# expansion.net
KiCad netlist of a schematic drawn in Altium Designer
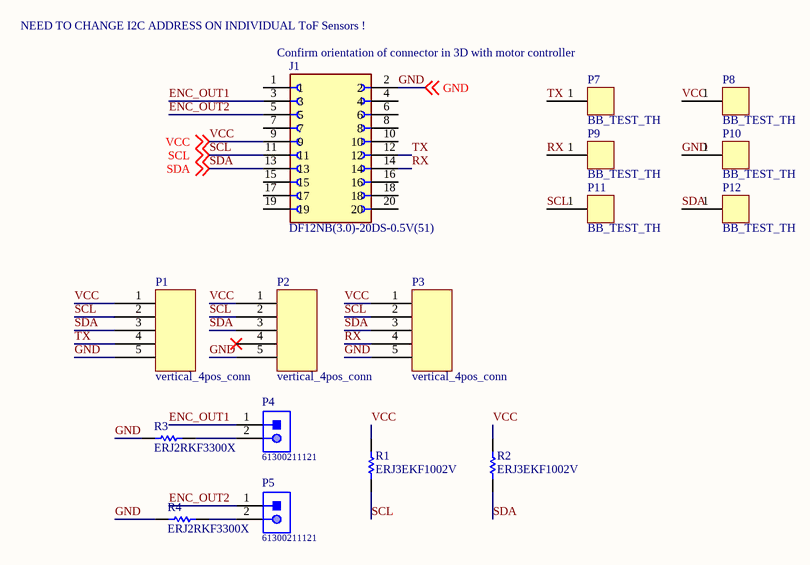
[diagram p0: expansion.SchDoc]

(export (version "E")
  (design (tool "Eeschema 10.0.6"))
  (components
    (comp (ref "J1")
      (value "DF12NB(3.0)-20DS-0.5V(51)")
      (footprint "HRS_DF12NB(3.0)-20DS-0.5V(51)")
      (libsource (lib "expansion_library") (part "DF12NB(3.0)-20DS-0.5V(51)"))
    )
    (comp (ref "P1")
      (value "vertical_4pos_conn")
      (footprint "vertical_4pos_conn _s_square")
      (libsource (lib "expansion_library") (part "vertical_4pos_conn"))
    )
    (comp (ref "P2")
      (value "vertical_4pos_conn")
      (footprint "vertical_4pos_conn _s_square")
      (libsource (lib "expansion_library") (part "vertical_4pos_conn"))
    )
    (comp (ref "P3")
      (value "vertical_4pos_conn")
      (footprint "vertical_4pos_conn _s_square")
      (libsource (lib "expansion_library") (part "vertical_4pos_conn"))
    )
    (comp (ref "P4")
      (value "61300211121")
      (footprint "61300211121")
      (description "THT Vertical Pin Header WR-PHD, Pitch 2.54 mm, Single Row, 2 pins")
      (fields (field (name "MANUFACTURER") "Wurth Elektronik") (field (name "PUBLISHER") "WurthElektronik"))
      (libsource (lib "Altium Content Vault") (part "WE-CN-1P-M-R2"))
    )
    (comp (ref "P5")
      (value "61300211121")
      (footprint "61300211121")
      (description "THT Vertical Pin Header WR-PHD, Pitch 2.54 mm, Single Row, 2 pins")
      (fields (field (name "MANUFACTURER") "Wurth Elektronik") (field (name "PUBLISHER") "WurthElektronik"))
      (libsource (lib "Altium Content Vault") (part "WE-CN-1P-M-R2"))
    )
    (comp (ref "P7")
      (value "BB_TEST_TH")
      (footprint "BB_WIRE_TEST_TH")
      (libsource (lib "expansion_library") (part "BB_TEST_TH"))
    )
    (comp (ref "P8")
      (value "BB_TEST_TH")
      (footprint "BB_WIRE_TEST_TH")
      (libsource (lib "expansion_library") (part "BB_TEST_TH"))
    )
    (comp (ref "P9")
      (value "BB_TEST_TH")
      (footprint "BB_WIRE_TEST_TH")
      (libsource (lib "expansion_library") (part "BB_TEST_TH"))
    )
    (comp (ref "P10")
      (value "BB_TEST_TH")
      (footprint "BB_WIRE_TEST_TH")
      (libsource (lib "expansion_library") (part "BB_TEST_TH"))
    )
    (comp (ref "P11")
      (value "BB_TEST_TH")
      (footprint "BB_WIRE_TEST_TH")
      (libsource (lib "expansion_library") (part "BB_TEST_TH"))
    )
    (comp (ref "P12")
      (value "BB_TEST_TH")
      (footprint "BB_WIRE_TEST_TH")
      (libsource (lib "expansion_library") (part "BB_TEST_TH"))
    )
    (comp (ref "R1")
      (value "ERJ3EKF1002V")
      (footprint "RESC1609X55X30LL15T15")
      (description "Chip Resistor, 10 KOhm, +/- 1%, 0.1 W, -55 to 155 degC, 0603 (1608 Metric), RoHS, Tape and Reel")
      (fields (field (name "TOLERANCE") "1%") (field (name "MANUFACTURER") "Panasonic"))
      (libsource (lib "Altium Content Vault") (part "RES-2"))
    )
    (comp (ref "R2")
      (value "ERJ3EKF1002V")
      (footprint "RESC1609X55X30LL15T15")
      (description "Chip Resistor, 10 KOhm, +/- 1%, 0.1 W, -55 to 155 degC, 0603 (1608 Metric), RoHS, Tape and Reel")
      (fields (field (name "TOLERANCE") "1%") (field (name "MANUFACTURER") "Panasonic"))
      (libsource (lib "Altium Content Vault") (part "RES-2"))
    )
    (comp (ref "R3")
      (value "ERJ2RKF3300X")
      (footprint "RESC1005X40X25ML05T05")
      (fields (field (name "MANUFACTURER") "Panasonic"))
      (libsource (lib "Altium Content Vault") (part "RES"))
    )
    (comp (ref "R4")
      (value "ERJ2RKF3300X")
      (footprint "RESC1005X40X25ML05T05")
      (fields (field (name "MANUFACTURER") "Panasonic"))
      (libsource (lib "Altium Content Vault") (part "RES"))
    )
  )
  (nets
    (net (code "1") (name "/ENC_OUT1") (class "Default")
      (node (ref "J1") (pin "3") (pinfunction "3_3") (pintype "passive"))
      (node (ref "P4") (pin "1") (pinfunction "1_1") (pintype "passive"))
    )
    (net (code "2") (name "/ENC_OUT2") (class "Default")
      (node (ref "J1") (pin "5") (pinfunction "5_5") (pintype "passive"))
      (node (ref "P5") (pin "1") (pinfunction "1_1") (pintype "passive"))
    )
    (net (code "3") (name "/RX") (class "Default")
      (node (ref "J1") (pin "14") (pinfunction "14_14") (pintype "passive"))
      (node (ref "P3") (pin "4") (pinfunction "4_4") (pintype "passive"))
      (node (ref "P9") (pin "1") (pinfunction "1_1") (pintype "passive"))
    )
    (net (code "4") (name "/TX") (class "Default")
      (node (ref "J1") (pin "12") (pinfunction "12_12") (pintype "passive"))
      (node (ref "P1") (pin "4") (pinfunction "4_4") (pintype "passive"))
      (node (ref "P7") (pin "1") (pinfunction "1_1") (pintype "passive"))
    )
    (net (code "5") (name "GND") (class "Default")
      (node (ref "J1") (pin "2") (pinfunction "2_2") (pintype "passive"))
      (node (ref "P1") (pin "5") (pinfunction "5_5") (pintype "passive"))
      (node (ref "P10") (pin "1") (pinfunction "1_1") (pintype "passive"))
      (node (ref "P2") (pin "5") (pinfunction "5_5") (pintype "passive"))
      (node (ref "P3") (pin "5") (pinfunction "5_5") (pintype "passive"))
      (node (ref "R3") (pin "1") (pinfunction "1_1") (pintype "passive"))
      (node (ref "R4") (pin "1") (pinfunction "1_1") (pintype "passive"))
    )
    (net (code "6") (name "Net-(P4-Pad2)") (class "Default")
      (node (ref "P4") (pin "2") (pinfunction "2_2") (pintype "passive"))
      (node (ref "R3") (pin "2") (pinfunction "2_2") (pintype "passive"))
    )
    (net (code "7") (name "Net-(P5-Pad2)") (class "Default")
      (node (ref "P5") (pin "2") (pinfunction "2_2") (pintype "passive"))
      (node (ref "R4") (pin "2") (pinfunction "2_2") (pintype "passive"))
    )
    (net (code "8") (name "SCL") (class "Default")
      (node (ref "J1") (pin "11") (pinfunction "11_11") (pintype "passive"))
      (node (ref "P1") (pin "2") (pinfunction "2_2") (pintype "passive"))
      (node (ref "P11") (pin "1") (pinfunction "1_1") (pintype "passive"))
      (node (ref "P2") (pin "2") (pinfunction "2_2") (pintype "passive"))
      (node (ref "P3") (pin "2") (pinfunction "2_2") (pintype "passive"))
      (node (ref "R1") (pin "1") (pinfunction "1_1") (pintype "passive"))
    )
    (net (code "9") (name "SDA") (class "Default")
      (node (ref "J1") (pin "13") (pinfunction "13_13") (pintype "passive"))
      (node (ref "P1") (pin "3") (pinfunction "3_3") (pintype "passive"))
      (node (ref "P12") (pin "1") (pinfunction "1_1") (pintype "passive"))
      (node (ref "P2") (pin "3") (pinfunction "3_3") (pintype "passive"))
      (node (ref "P3") (pin "3") (pinfunction "3_3") (pintype "passive"))
      (node (ref "R2") (pin "1") (pinfunction "1_1") (pintype "passive"))
    )
    (net (code "10") (name "VCC") (class "Default")
      (node (ref "J1") (pin "9") (pinfunction "9_9") (pintype "passive"))
      (node (ref "P1") (pin "1") (pinfunction "1_1") (pintype "passive"))
      (node (ref "P2") (pin "1") (pinfunction "1_1") (pintype "passive"))
      (node (ref "P3") (pin "1") (pinfunction "1_1") (pintype "passive"))
      (node (ref "P8") (pin "1") (pinfunction "1_1") (pintype "passive"))
      (node (ref "R1") (pin "2") (pinfunction "2_2") (pintype "passive"))
      (node (ref "R2") (pin "2") (pinfunction "2_2") (pintype "passive"))
    )
    (net (code "11") (name "unconnected-(J1-Pad1)") (class "Default")
      (node (ref "J1") (pin "1") (pinfunction "1_1") (pintype "passive"))
    )
    (net (code "12") (name "unconnected-(J1-Pad4)") (class "Default")
      (node (ref "J1") (pin "4") (pinfunction "4_4") (pintype "passive"))
    )
    (net (code "13") (name "unconnected-(J1-Pad6)") (class "Default")
      (node (ref "J1") (pin "6") (pinfunction "6_6") (pintype "passive"))
    )
    (net (code "14") (name "unconnected-(J1-Pad7)") (class "Default")
      (node (ref "J1") (pin "7") (pinfunction "7_7") (pintype "passive"))
    )
    (net (code "15") (name "unconnected-(J1-Pad8)") (class "Default")
      (node (ref "J1") (pin "8") (pinfunction "8_8") (pintype "passive"))
    )
    (net (code "16") (name "unconnected-(J1-Pad10)") (class "Default")
      (node (ref "J1") (pin "10") (pinfunction "10_10") (pintype "passive"))
    )
    (net (code "17") (name "unconnected-(J1-Pad15)") (class "Default")
      (node (ref "J1") (pin "15") (pinfunction "15_15") (pintype "passive"))
    )
    (net (code "18") (name "unconnected-(J1-Pad16)") (class "Default")
      (node (ref "J1") (pin "16") (pinfunction "16_16") (pintype "passive"))
    )
    (net (code "19") (name "unconnected-(J1-Pad17)") (class "Default")
      (node (ref "J1") (pin "17") (pinfunction "17_17") (pintype "passive"))
    )
    (net (code "20") (name "unconnected-(J1-Pad18)") (class "Default")
      (node (ref "J1") (pin "18") (pinfunction "18_18") (pintype "passive"))
    )
    (net (code "21") (name "unconnected-(J1-Pad19)") (class "Default")
      (node (ref "J1") (pin "19") (pinfunction "19_19") (pintype "passive"))
    )
    (net (code "22") (name "unconnected-(J1-Pad20)") (class "Default")
      (node (ref "J1") (pin "20") (pinfunction "20_20") (pintype "passive"))
    )
    (net (code "23") (name "unconnected-(P2-Pad4)") (class "Default")
      (node (ref "P2") (pin "4") (pinfunction "4_4") (pintype "passive+no_connect"))
    )
  )
)
